# Remote.net
KiCad netlist of a schematic drawn in EAGLE
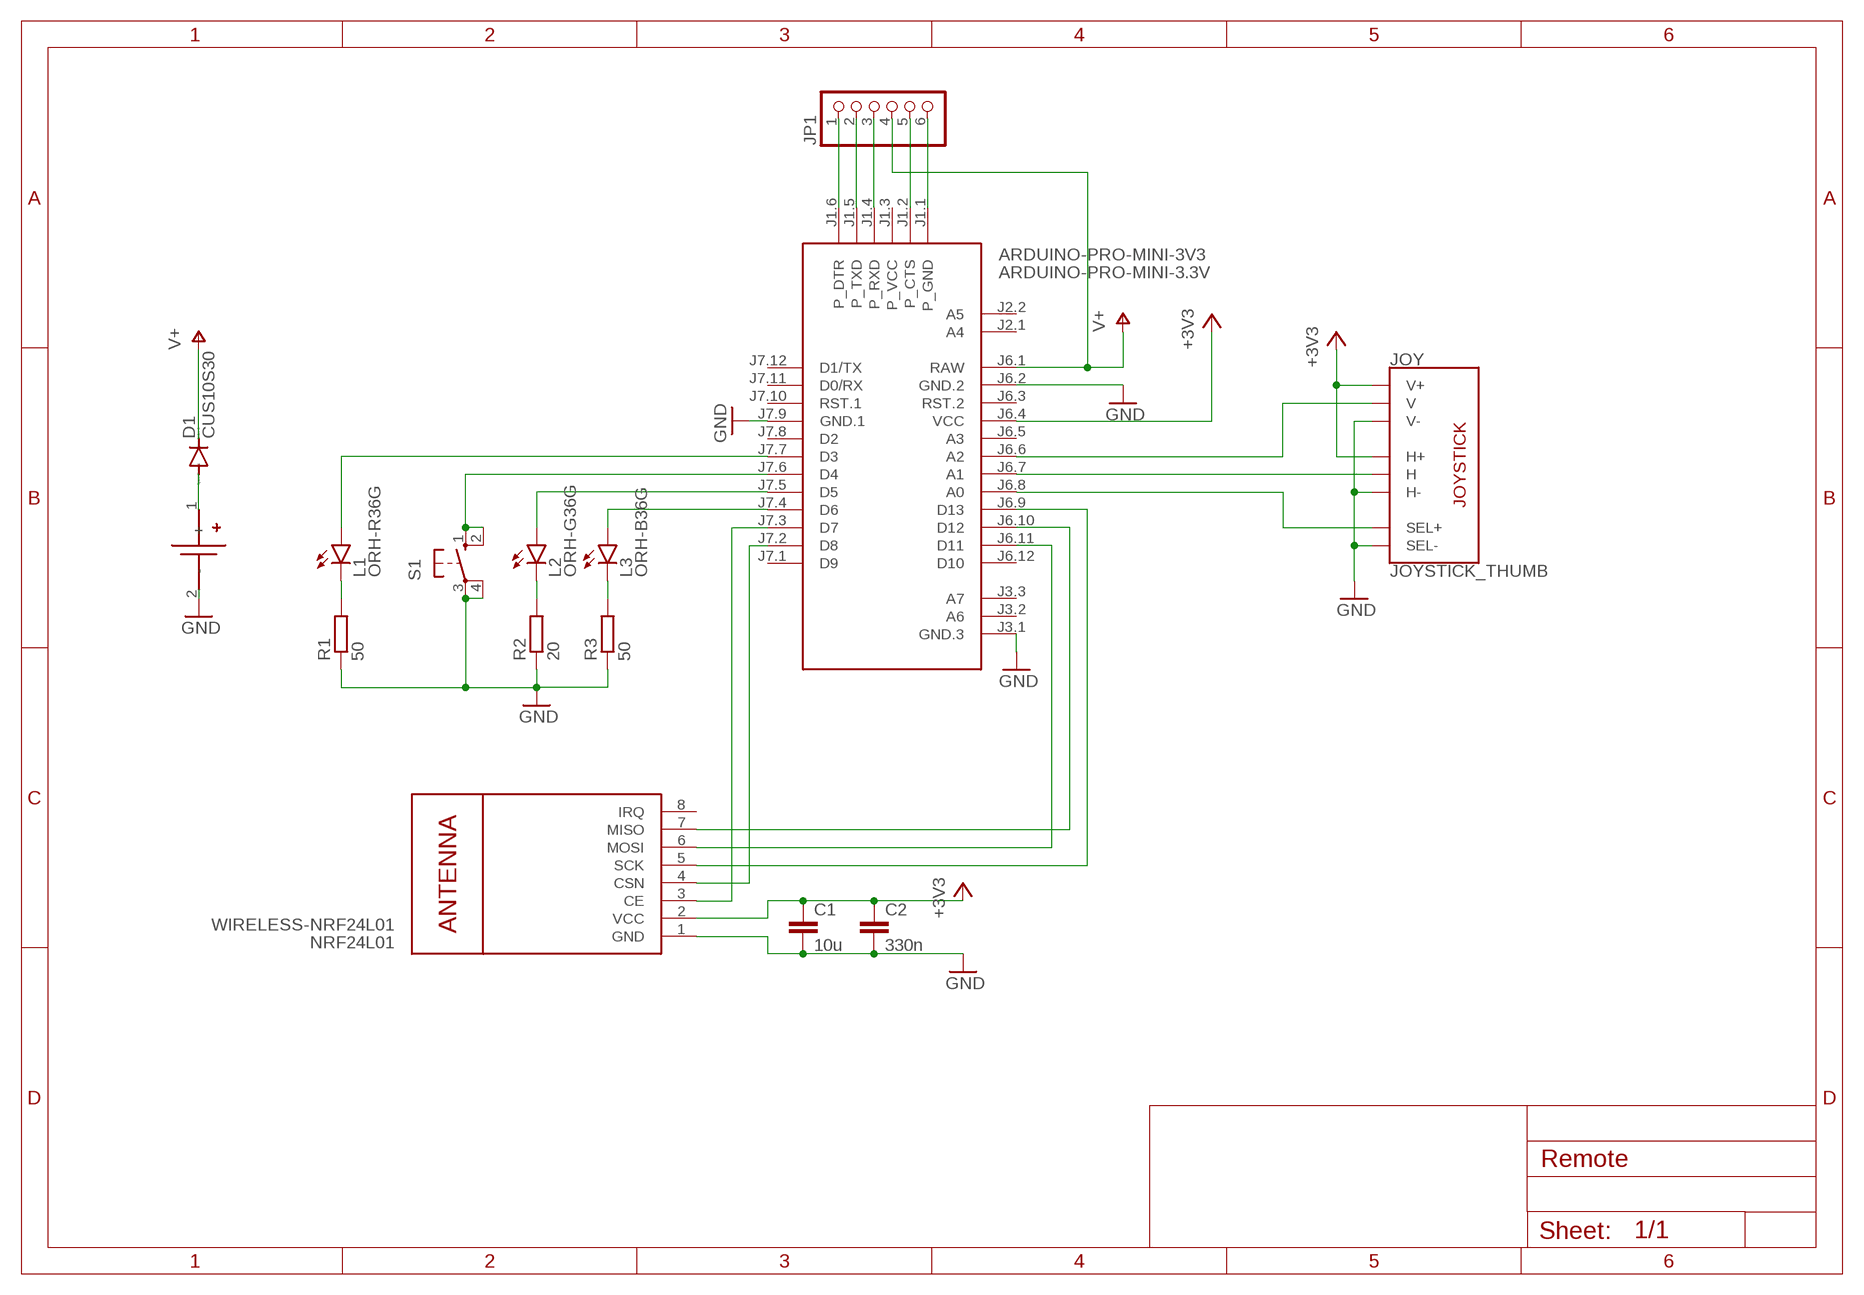
[diagram p0: schematic, sheet 1]

(export (version "E")
  (design (tool "Eeschema 10.0.6"))
  (components
    (comp (ref "ARDUINO-PRO-MINI-3V3")
      (value "ARDUINO-PRO-MINI-3.3V")
      (footprint "eagle-import:ARDUINO-PRO-MINI")
      (libsource (lib "eagle-import") (part "ARDUINO-PRO-MINI-3.3V"))
    )
    (comp (ref "C1")
      (value "10u")
      (footprint "eagle-import:C0805")
      (libsource (lib "eagle-import") (part "C-EUC0805"))
    )
    (comp (ref "C2")
      (value "330n")
      (footprint "eagle-import:C0805")
      (libsource (lib "eagle-import") (part "C-EUC0805"))
    )
    (comp (ref "D1")
      (value "CUS10S30")
      (footprint "eagle-import:SOD323-W")
      (libsource (lib "eagle-import") (part "DIODE-SOD323-W"))
    )
    (comp (ref "JOY")
      (value "JOYSTICK_THUMB")
      (footprint "eagle-import:JOYSTICK")
      (libsource (lib "eagle-import") (part "JOYSTICK_THUMB"))
    )
    (comp (ref "JP1")
      (value "PINHD-1X6")
      (footprint "eagle-import:1X06")
      (libsource (lib "eagle-import") (part "PINHD-1X6"))
    )
    (comp (ref "L1")
      (value "ORH-R36G")
      (footprint "eagle-import:CHIP-LED0603")
      (libsource (lib "eagle-import") (part "LEDCHIP-LED0603"))
    )
    (comp (ref "L2")
      (value "ORH-G36G")
      (footprint "eagle-import:CHIP-LED0603")
      (libsource (lib "eagle-import") (part "LEDCHIP-LED0603"))
    )
    (comp (ref "L3")
      (value "ORH-B36G")
      (footprint "eagle-import:CHIP-LED0603")
      (libsource (lib "eagle-import") (part "LEDCHIP-LED0603"))
    )
    (comp (ref "NRF24L01")
      (value "WIRELESS-NRF24L01")
      (footprint "eagle-import:WIRELESS-NRF24L01")
      (libsource (lib "eagle-import") (part "WIRELESS-NRF24L01"))
    )
    (comp (ref "R1")
      (value "50")
      (footprint "eagle-import:R0603")
      (libsource (lib "eagle-import") (part "R-EU_R0603"))
    )
    (comp (ref "R2")
      (value "20")
      (footprint "eagle-import:R0603")
      (libsource (lib "eagle-import") (part "R-EU_R0603"))
    )
    (comp (ref "R3")
      (value "50")
      (footprint "eagle-import:R0603")
      (libsource (lib "eagle-import") (part "R-EU_R0603"))
    )
    (comp (ref "S1")
      (value "10-XX")
      (footprint "eagle-import:B3F-10XX")
      (fields (field (name "MPN") "B3F-1000"))
      (libsource (lib "eagle-import") (part "10-XX"))
    )
    (comp (ref "U$2")
      (value "BLOSSOM-BLM-18650-1PCSNO-SCREWS")
      (footprint "eagle-import:BLOSSOM-BLM-18650-1PCS-NO-SCREWS-SMALL-HOLES")
      (libsource (lib "eagle-import") (part "BLOSSOM-BLM-18650-1PCSNO-SCREWS"))
    )
  )
  (nets
    (net (code "1") (name "+3V3") (class "Default")
      (node (ref "ARDUINO-PRO-MINI-3V3") (pin "J6.4") (pinfunction "VCC_J6.4") (pintype "power_in"))
      (node (ref "C1") (pin "1") (pinfunction "1_1") (pintype "passive"))
      (node (ref "C2") (pin "1") (pinfunction "1_1") (pintype "passive"))
      (node (ref "JOY") (pin "H1") (pinfunction "H+_H1") (pintype "bidirectional"))
      (node (ref "JOY") (pin "V1") (pinfunction "V+_V1") (pintype "bidirectional"))
      (node (ref "NRF24L01") (pin "2") (pinfunction "VCC_2") (pintype "power_in"))
    )
    (net (code "2") (name "GND") (class "Default")
      (node (ref "ARDUINO-PRO-MINI-3V3") (pin "J3.1") (pinfunction "GND.3_J3.1") (pintype "bidirectional"))
      (node (ref "ARDUINO-PRO-MINI-3V3") (pin "J6.2") (pinfunction "GND.2_J6.2") (pintype "power_in"))
      (node (ref "ARDUINO-PRO-MINI-3V3") (pin "J7.9") (pinfunction "GND.1_J7.9") (pintype "power_in"))
      (node (ref "C1") (pin "2") (pinfunction "2_2") (pintype "passive"))
      (node (ref "C2") (pin "2") (pinfunction "2_2") (pintype "passive"))
      (node (ref "JOY") (pin "B2A") (pinfunction "SEL-_B2A") (pintype "bidirectional"))
      (node (ref "JOY") (pin "H3") (pinfunction "H-_H3") (pintype "bidirectional"))
      (node (ref "JOY") (pin "V3") (pinfunction "V-_V3") (pintype "bidirectional"))
      (node (ref "NRF24L01") (pin "1") (pinfunction "GND_1") (pintype "power_in"))
      (node (ref "R1") (pin "1") (pinfunction "1_1") (pintype "passive"))
      (node (ref "R2") (pin "1") (pinfunction "1_1") (pintype "passive"))
      (node (ref "R3") (pin "1") (pinfunction "1_1") (pintype "passive"))
      (node (ref "S1") (pin "3") (pinfunction "P_3") (pintype "passive"))
      (node (ref "S1") (pin "4") (pinfunction "P1_4") (pintype "passive"))
      (node (ref "U$2") (pin "2") (pinfunction "-_2") (pintype "bidirectional"))
    )
    (net (code "3") (name "Net-(ARDUINO-PRO-MINI-3V3-A0)") (class "Default")
      (node (ref "ARDUINO-PRO-MINI-3V3") (pin "J6.8") (pinfunction "A0_J6.8") (pintype "bidirectional"))
      (node (ref "JOY") (pin "B1A") (pinfunction "SEL+_B1A") (pintype "bidirectional"))
    )
    (net (code "4") (name "Net-(ARDUINO-PRO-MINI-3V3-A1)") (class "Default")
      (node (ref "ARDUINO-PRO-MINI-3V3") (pin "J6.7") (pinfunction "A1_J6.7") (pintype "bidirectional"))
      (node (ref "JOY") (pin "H2") (pinfunction "H_H2") (pintype "bidirectional"))
    )
    (net (code "5") (name "Net-(ARDUINO-PRO-MINI-3V3-A2)") (class "Default")
      (node (ref "ARDUINO-PRO-MINI-3V3") (pin "J6.6") (pinfunction "A2_J6.6") (pintype "bidirectional"))
      (node (ref "JOY") (pin "V2") (pinfunction "V_V2") (pintype "bidirectional"))
    )
    (net (code "6") (name "Net-(ARDUINO-PRO-MINI-3V3-D3)") (class "Default")
      (node (ref "ARDUINO-PRO-MINI-3V3") (pin "J7.7") (pinfunction "D3_J7.7") (pintype "bidirectional"))
      (node (ref "L1") (pin "A") (pinfunction "A_A") (pintype "passive"))
    )
    (net (code "7") (name "Net-(ARDUINO-PRO-MINI-3V3-D4)") (class "Default")
      (node (ref "ARDUINO-PRO-MINI-3V3") (pin "J7.6") (pinfunction "D4_J7.6") (pintype "bidirectional"))
      (node (ref "S1") (pin "1") (pinfunction "S_1") (pintype "passive"))
      (node (ref "S1") (pin "2") (pinfunction "S1_2") (pintype "passive"))
    )
    (net (code "8") (name "Net-(ARDUINO-PRO-MINI-3V3-D5)") (class "Default")
      (node (ref "ARDUINO-PRO-MINI-3V3") (pin "J7.5") (pinfunction "D5_J7.5") (pintype "bidirectional"))
      (node (ref "L2") (pin "A") (pinfunction "A_A") (pintype "passive"))
    )
    (net (code "9") (name "Net-(ARDUINO-PRO-MINI-3V3-D6)") (class "Default")
      (node (ref "ARDUINO-PRO-MINI-3V3") (pin "J7.4") (pinfunction "D6_J7.4") (pintype "bidirectional"))
      (node (ref "L3") (pin "A") (pinfunction "A_A") (pintype "passive"))
    )
    (net (code "10") (name "Net-(ARDUINO-PRO-MINI-3V3-D7)") (class "Default")
      (node (ref "ARDUINO-PRO-MINI-3V3") (pin "J7.3") (pinfunction "D7_J7.3") (pintype "bidirectional"))
      (node (ref "NRF24L01") (pin "3") (pinfunction "CE_3") (pintype "bidirectional"))
    )
    (net (code "11") (name "Net-(ARDUINO-PRO-MINI-3V3-D8)") (class "Default")
      (node (ref "ARDUINO-PRO-MINI-3V3") (pin "J7.2") (pinfunction "D8_J7.2") (pintype "bidirectional"))
      (node (ref "NRF24L01") (pin "4") (pinfunction "CSN_4") (pintype "bidirectional"))
    )
    (net (code "12") (name "Net-(ARDUINO-PRO-MINI-3V3-D11)") (class "Default")
      (node (ref "ARDUINO-PRO-MINI-3V3") (pin "J6.11") (pinfunction "D11_J6.11") (pintype "bidirectional"))
      (node (ref "NRF24L01") (pin "6") (pinfunction "MOSI_6") (pintype "bidirectional"))
    )
    (net (code "13") (name "Net-(ARDUINO-PRO-MINI-3V3-D12)") (class "Default")
      (node (ref "ARDUINO-PRO-MINI-3V3") (pin "J6.10") (pinfunction "D12_J6.10") (pintype "bidirectional"))
      (node (ref "NRF24L01") (pin "7") (pinfunction "MISO_7") (pintype "bidirectional"))
    )
    (net (code "14") (name "Net-(ARDUINO-PRO-MINI-3V3-D13)") (class "Default")
      (node (ref "ARDUINO-PRO-MINI-3V3") (pin "J6.9") (pinfunction "D13_J6.9") (pintype "bidirectional"))
      (node (ref "NRF24L01") (pin "5") (pinfunction "SCK_5") (pintype "bidirectional"))
    )
    (net (code "15") (name "Net-(ARDUINO-PRO-MINI-3V3-P_CTS)") (class "Default")
      (node (ref "ARDUINO-PRO-MINI-3V3") (pin "J1.2") (pinfunction "P_CTS_J1.2") (pintype "bidirectional"))
      (node (ref "JP1") (pin "5") (pinfunction "5_5") (pintype "passive"))
    )
    (net (code "16") (name "Net-(ARDUINO-PRO-MINI-3V3-P_DTR)") (class "Default")
      (node (ref "ARDUINO-PRO-MINI-3V3") (pin "J1.6") (pinfunction "P_DTR_J1.6") (pintype "bidirectional"))
      (node (ref "JP1") (pin "1") (pinfunction "1_1") (pintype "passive"))
    )
    (net (code "17") (name "Net-(ARDUINO-PRO-MINI-3V3-P_GND)") (class "Default")
      (node (ref "ARDUINO-PRO-MINI-3V3") (pin "J1.1") (pinfunction "P_GND_J1.1") (pintype "bidirectional"))
      (node (ref "JP1") (pin "6") (pinfunction "6_6") (pintype "passive"))
    )
    (net (code "18") (name "Net-(ARDUINO-PRO-MINI-3V3-P_RXD)") (class "Default")
      (node (ref "ARDUINO-PRO-MINI-3V3") (pin "J1.4") (pinfunction "P_RXD_J1.4") (pintype "bidirectional"))
      (node (ref "JP1") (pin "3") (pinfunction "3_3") (pintype "passive"))
    )
    (net (code "19") (name "Net-(ARDUINO-PRO-MINI-3V3-P_TXD)") (class "Default")
      (node (ref "ARDUINO-PRO-MINI-3V3") (pin "J1.5") (pinfunction "P_TXD_J1.5") (pintype "bidirectional"))
      (node (ref "JP1") (pin "2") (pinfunction "2_2") (pintype "passive"))
    )
    (net (code "20") (name "Net-(L1-PadC)") (class "Default")
      (node (ref "L1") (pin "C") (pinfunction "C_C") (pintype "passive"))
      (node (ref "R1") (pin "2") (pinfunction "2_2") (pintype "passive"))
    )
    (net (code "21") (name "Net-(L2-PadC)") (class "Default")
      (node (ref "L2") (pin "C") (pinfunction "C_C") (pintype "passive"))
      (node (ref "R2") (pin "2") (pinfunction "2_2") (pintype "passive"))
    )
    (net (code "22") (name "Net-(L3-PadC)") (class "Default")
      (node (ref "L3") (pin "C") (pinfunction "C_C") (pintype "passive"))
      (node (ref "R3") (pin "2") (pinfunction "2_2") (pintype "passive"))
    )
    (net (code "23") (name "Net-(U$2-+)") (class "Default")
      (node (ref "D1") (pin "A") (pinfunction "A_A") (pintype "passive"))
      (node (ref "U$2") (pin "1") (pinfunction "+_1") (pintype "bidirectional"))
    )
    (net (code "24") (name "V+") (class "Default")
      (node (ref "ARDUINO-PRO-MINI-3V3") (pin "J6.1") (pinfunction "RAW_J6.1") (pintype "power_in"))
      (node (ref "D1") (pin "C") (pinfunction "C_C") (pintype "passive"))
      (node (ref "JP1") (pin "4") (pinfunction "4_4") (pintype "passive"))
    )
    (net (code "25") (name "unconnected-(ARDUINO-PRO-MINI-3V3-A3-PadJ6.5)") (class "Default")
      (node (ref "ARDUINO-PRO-MINI-3V3") (pin "J6.5") (pinfunction "A3_J6.5") (pintype "bidirectional"))
    )
    (net (code "26") (name "unconnected-(ARDUINO-PRO-MINI-3V3-A4-PadJ2.1)") (class "Default")
      (node (ref "ARDUINO-PRO-MINI-3V3") (pin "J2.1") (pinfunction "A4_J2.1") (pintype "bidirectional"))
    )
    (net (code "27") (name "unconnected-(ARDUINO-PRO-MINI-3V3-A5-PadJ2.2)") (class "Default")
      (node (ref "ARDUINO-PRO-MINI-3V3") (pin "J2.2") (pinfunction "A5_J2.2") (pintype "bidirectional"))
    )
    (net (code "28") (name "unconnected-(ARDUINO-PRO-MINI-3V3-A6-PadJ3.2)") (class "Default")
      (node (ref "ARDUINO-PRO-MINI-3V3") (pin "J3.2") (pinfunction "A6_J3.2") (pintype "bidirectional"))
    )
    (net (code "29") (name "unconnected-(ARDUINO-PRO-MINI-3V3-A7-PadJ3.3)") (class "Default")
      (node (ref "ARDUINO-PRO-MINI-3V3") (pin "J3.3") (pinfunction "A7_J3.3") (pintype "bidirectional"))
    )
    (net (code "30") (name "unconnected-(ARDUINO-PRO-MINI-3V3-D0{slash}RX-PadJ7.11)") (class "Default")
      (node (ref "ARDUINO-PRO-MINI-3V3") (pin "J7.11") (pinfunction "D0/RX_J7.11") (pintype "bidirectional"))
    )
    (net (code "31") (name "unconnected-(ARDUINO-PRO-MINI-3V3-D1{slash}TX-PadJ7.12)") (class "Default")
      (node (ref "ARDUINO-PRO-MINI-3V3") (pin "J7.12") (pinfunction "D1/TX_J7.12") (pintype "bidirectional"))
    )
    (net (code "32") (name "unconnected-(ARDUINO-PRO-MINI-3V3-D2-PadJ7.8)") (class "Default")
      (node (ref "ARDUINO-PRO-MINI-3V3") (pin "J7.8") (pinfunction "D2_J7.8") (pintype "bidirectional"))
    )
    (net (code "33") (name "unconnected-(ARDUINO-PRO-MINI-3V3-D9-PadJ7.1)") (class "Default")
      (node (ref "ARDUINO-PRO-MINI-3V3") (pin "J7.1") (pinfunction "D9_J7.1") (pintype "bidirectional"))
    )
    (net (code "34") (name "unconnected-(ARDUINO-PRO-MINI-3V3-D10-PadJ6.12)") (class "Default")
      (node (ref "ARDUINO-PRO-MINI-3V3") (pin "J6.12") (pinfunction "D10_J6.12") (pintype "bidirectional"))
    )
    (net (code "35") (name "unconnected-(ARDUINO-PRO-MINI-3V3-P_VCC-PadJ1.3)") (class "Default")
      (node (ref "ARDUINO-PRO-MINI-3V3") (pin "J1.3") (pinfunction "P_VCC_J1.3") (pintype "bidirectional"))
    )
    (net (code "36") (name "unconnected-(ARDUINO-PRO-MINI-3V3-RST.1-PadJ7.10)") (class "Default")
      (node (ref "ARDUINO-PRO-MINI-3V3") (pin "J7.10") (pinfunction "RST.1_J7.10") (pintype "bidirectional"))
    )
    (net (code "37") (name "unconnected-(ARDUINO-PRO-MINI-3V3-RST.2-PadJ6.3)") (class "Default")
      (node (ref "ARDUINO-PRO-MINI-3V3") (pin "J6.3") (pinfunction "RST.2_J6.3") (pintype "bidirectional"))
    )
    (net (code "38") (name "unconnected-(NRF24L01-IRQ-Pad8)") (class "Default")
      (node (ref "NRF24L01") (pin "8") (pinfunction "IRQ_8") (pintype "bidirectional"))
    )
  )
)
